# Moisture_Gauge.net
KiCad netlist of a schematic drawn in EAGLE
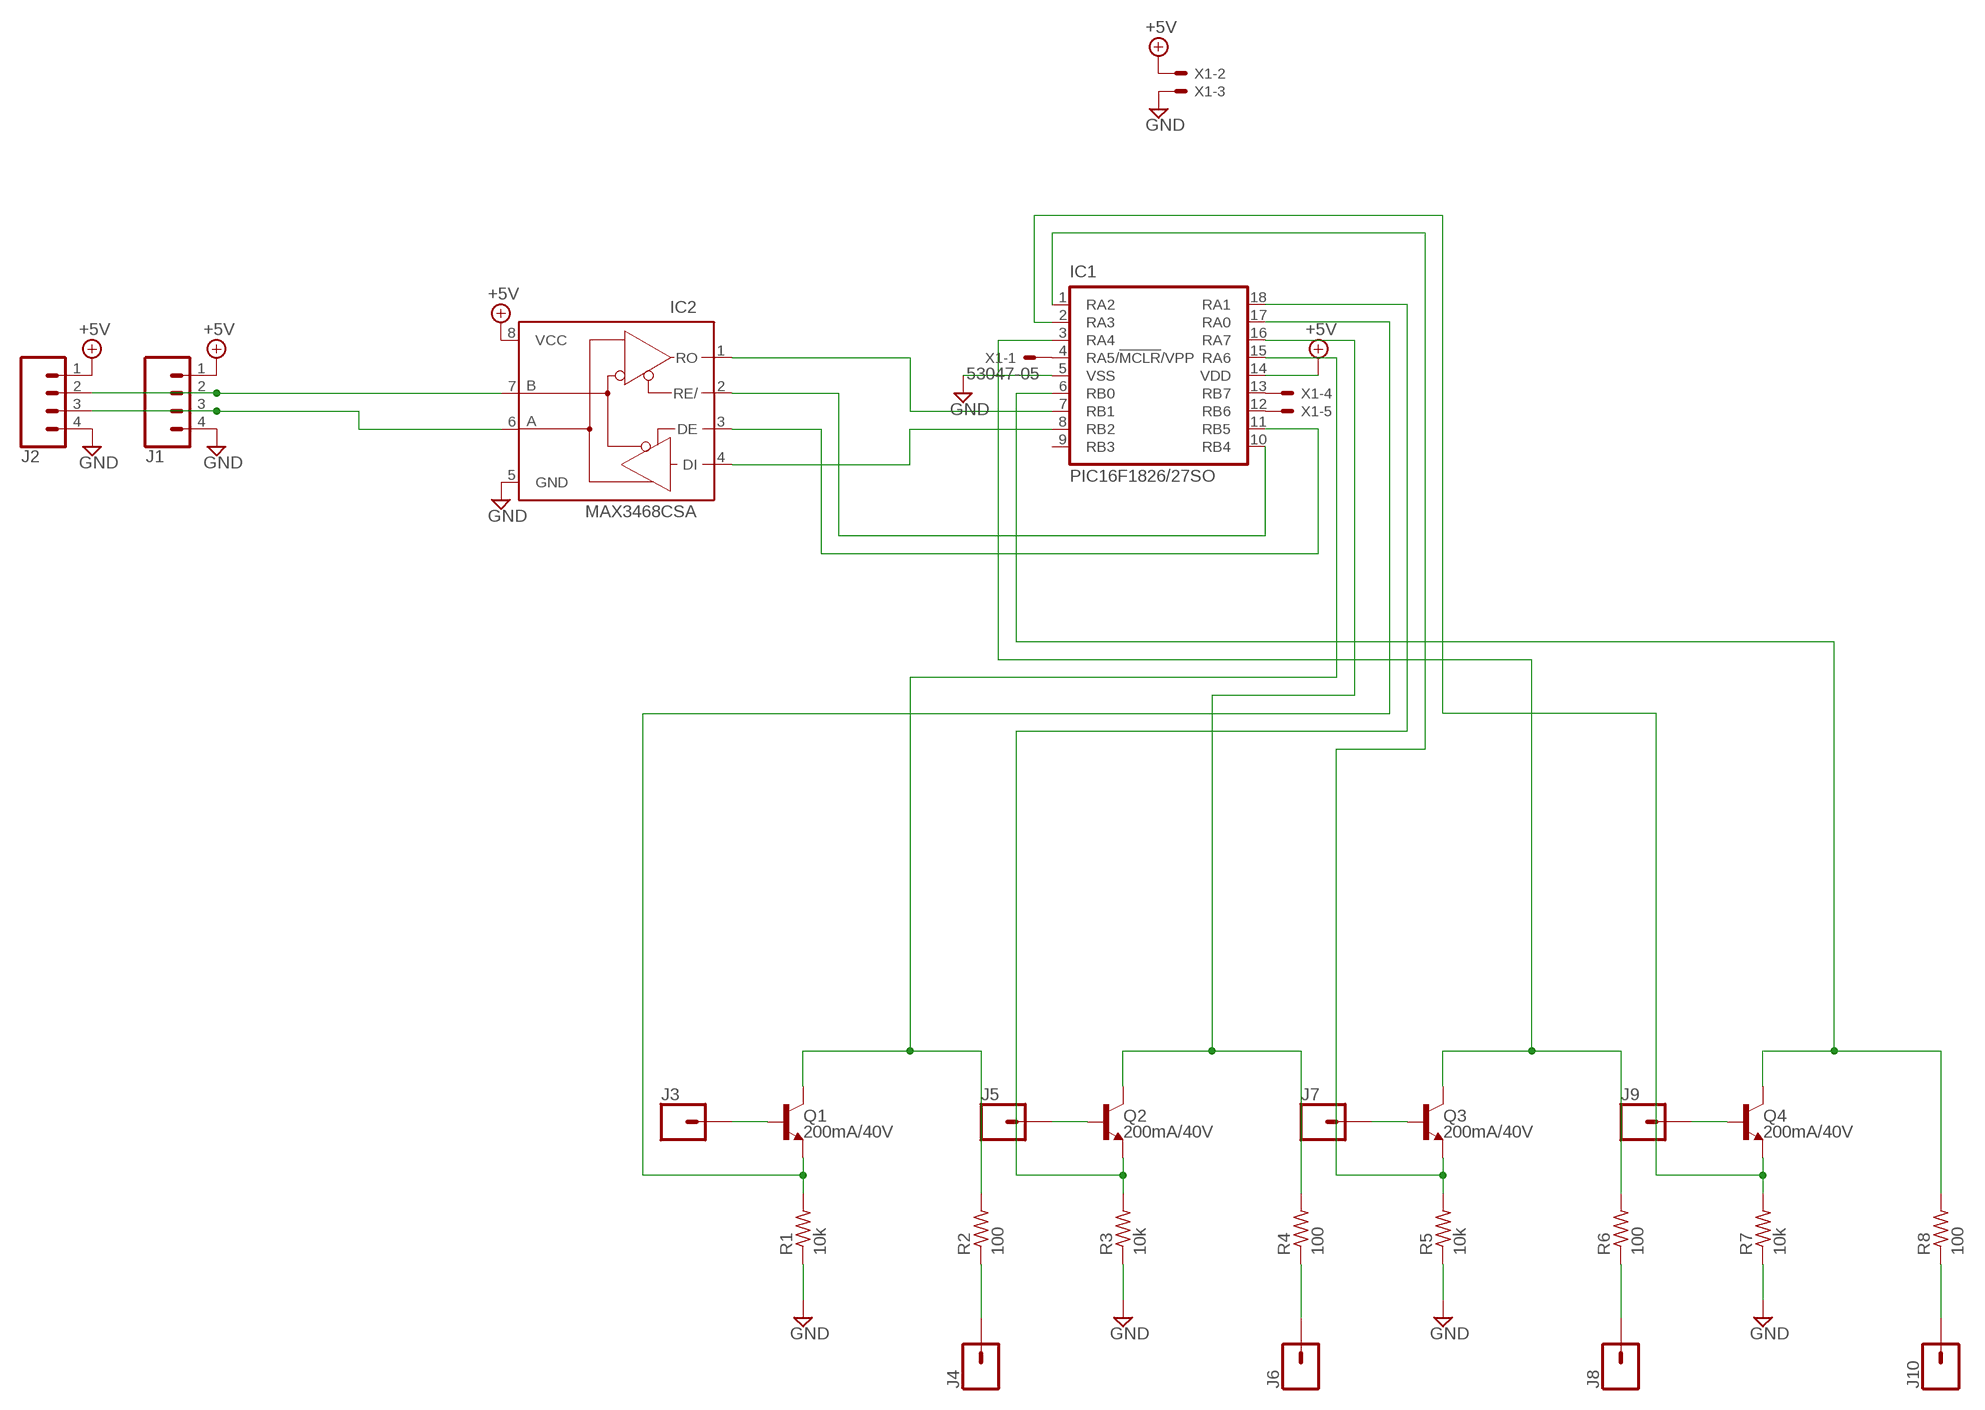
[diagram p0: schematic, sheet 1]

(export (version "E")
  (design (tool "Eeschema 10.0.6"))
  (components
    (comp (ref "IC1")
      (value "PIC16F1826/27SO")
      (footprint "eagle-import:SO-18W")
      (libsource (lib "eagle-import") (part "PIC16F1826/27SO"))
    )
    (comp (ref "IC2")
      (value "MAX3468CSA")
      (footprint "eagle-import:SO08")
      (fields (field (name "MPN") "MAX3468CSA+"))
      (libsource (lib "eagle-import") (part "MAX34SA68C"))
    )
    (comp (ref "J1")
      (value "CONN_04SCREW")
      (footprint "eagle-import:SCREWTERMINAL-3.5MM-4")
      (libsource (lib "eagle-import") (part "CONN_04SCREW"))
    )
    (comp (ref "J2")
      (value "CONN_04SCREW")
      (footprint "eagle-import:SCREWTERMINAL-3.5MM-4")
      (libsource (lib "eagle-import") (part "CONN_04SCREW"))
    )
    (comp (ref "J3")
      (value "CONN_01PTH_2MM")
      (footprint "eagle-import:1X01_2MM")
      (libsource (lib "eagle-import") (part "CONN_01PTH_2MM"))
    )
    (comp (ref "J4")
      (value "CONN_01PTH_2MM")
      (footprint "eagle-import:1X01_2MM")
      (libsource (lib "eagle-import") (part "CONN_01PTH_2MM"))
    )
    (comp (ref "J5")
      (value "CONN_01PTH_2MM")
      (footprint "eagle-import:1X01_2MM")
      (libsource (lib "eagle-import") (part "CONN_01PTH_2MM"))
    )
    (comp (ref "J6")
      (value "CONN_01PTH_2MM")
      (footprint "eagle-import:1X01_2MM")
      (libsource (lib "eagle-import") (part "CONN_01PTH_2MM"))
    )
    (comp (ref "J7")
      (value "CONN_01PTH_2MM")
      (footprint "eagle-import:1X01_2MM")
      (libsource (lib "eagle-import") (part "CONN_01PTH_2MM"))
    )
    (comp (ref "J8")
      (value "CONN_01PTH_2MM")
      (footprint "eagle-import:1X01_2MM")
      (libsource (lib "eagle-import") (part "CONN_01PTH_2MM"))
    )
    (comp (ref "J9")
      (value "CONN_01PTH_2MM")
      (footprint "eagle-import:1X01_2MM")
      (libsource (lib "eagle-import") (part "CONN_01PTH_2MM"))
    )
    (comp (ref "J10")
      (value "CONN_01PTH_2MM")
      (footprint "eagle-import:1X01_2MM")
      (libsource (lib "eagle-import") (part "CONN_01PTH_2MM"))
    )
    (comp (ref "Q1")
      (value "200mA/40V")
      (footprint "eagle-import:TO-92")
      (libsource (lib "eagle-import") (part "TRANS_NPN-2N3904"))
    )
    (comp (ref "Q2")
      (value "200mA/40V")
      (footprint "eagle-import:TO-92")
      (libsource (lib "eagle-import") (part "TRANS_NPN-2N3904"))
    )
    (comp (ref "Q3")
      (value "200mA/40V")
      (footprint "eagle-import:TO-92")
      (libsource (lib "eagle-import") (part "TRANS_NPN-2N3904"))
    )
    (comp (ref "Q4")
      (value "200mA/40V")
      (footprint "eagle-import:TO-92")
      (libsource (lib "eagle-import") (part "TRANS_NPN-2N3904"))
    )
    (comp (ref "R1")
      (value "10k")
      (footprint "eagle-import:M1206")
      (libsource (lib "eagle-import") (part "R-US_M1206"))
    )
    (comp (ref "R2")
      (value "100")
      (footprint "eagle-import:M1206")
      (libsource (lib "eagle-import") (part "R-US_M1206"))
    )
    (comp (ref "R3")
      (value "10k")
      (footprint "eagle-import:M1206")
      (libsource (lib "eagle-import") (part "R-US_M1206"))
    )
    (comp (ref "R4")
      (value "100")
      (footprint "eagle-import:M1206")
      (libsource (lib "eagle-import") (part "R-US_M1206"))
    )
    (comp (ref "R5")
      (value "10k")
      (footprint "eagle-import:M1206")
      (libsource (lib "eagle-import") (part "R-US_M1206"))
    )
    (comp (ref "R6")
      (value "100")
      (footprint "eagle-import:M1206")
      (libsource (lib "eagle-import") (part "R-US_M1206"))
    )
    (comp (ref "R7")
      (value "10k")
      (footprint "eagle-import:M1206")
      (libsource (lib "eagle-import") (part "R-US_M1206"))
    )
    (comp (ref "R8")
      (value "100")
      (footprint "eagle-import:M1206")
      (libsource (lib "eagle-import") (part "R-US_M1206"))
    )
    (comp (ref "X1")
      (value "53047-05")
      (footprint "eagle-import:53047-05")
      (fields (field (name "MF") "MOLEX") (field (name "MPN") "53047-0510"))
      (libsource (lib "eagle-import") (part "53?-05047"))
    )
  )
  (nets
    (net (code "1") (name "+5V") (class "Default")
      (node (ref "IC1") (pin "14") (pinfunction "VDD_14") (pintype "power_in"))
      (node (ref "IC2") (pin "8") (pinfunction "VCC_8") (pintype "power_in"))
      (node (ref "J1") (pin "1") (pinfunction "1_1") (pintype "passive"))
      (node (ref "J2") (pin "1") (pinfunction "1_1") (pintype "passive"))
      (node (ref "X1") (pin "2") (pinfunction "S_2") (pintype "passive"))
    )
    (net (code "2") (name "GND") (class "Default")
      (node (ref "IC1") (pin "5") (pinfunction "VSS_5") (pintype "power_in"))
      (node (ref "IC2") (pin "5") (pinfunction "GND_5") (pintype "power_in"))
      (node (ref "J1") (pin "4") (pinfunction "4_4") (pintype "passive"))
      (node (ref "J2") (pin "4") (pinfunction "4_4") (pintype "passive"))
      (node (ref "R1") (pin "1") (pinfunction "1_1") (pintype "passive"))
      (node (ref "R3") (pin "1") (pinfunction "1_1") (pintype "passive"))
      (node (ref "R5") (pin "1") (pinfunction "1_1") (pintype "passive"))
      (node (ref "R7") (pin "1") (pinfunction "1_1") (pintype "passive"))
      (node (ref "X1") (pin "3") (pinfunction "S_3") (pintype "passive"))
    )
    (net (code "3") (name "Net-(IC1-RA0)") (class "Default")
      (node (ref "IC1") (pin "17") (pinfunction "RA0_17") (pintype "bidirectional"))
      (node (ref "Q1") (pin "1") (pinfunction "E_1") (pintype "passive"))
      (node (ref "R1") (pin "2") (pinfunction "2_2") (pintype "passive"))
    )
    (net (code "4") (name "Net-(IC1-RA1)") (class "Default")
      (node (ref "IC1") (pin "18") (pinfunction "RA1_18") (pintype "bidirectional"))
      (node (ref "Q2") (pin "1") (pinfunction "E_1") (pintype "passive"))
      (node (ref "R3") (pin "2") (pinfunction "2_2") (pintype "passive"))
    )
    (net (code "5") (name "Net-(IC1-RA2)") (class "Default")
      (node (ref "IC1") (pin "1") (pinfunction "RA2_1") (pintype "bidirectional"))
      (node (ref "Q3") (pin "1") (pinfunction "E_1") (pintype "passive"))
      (node (ref "R5") (pin "2") (pinfunction "2_2") (pintype "passive"))
    )
    (net (code "6") (name "Net-(IC1-RA3)") (class "Default")
      (node (ref "IC1") (pin "2") (pinfunction "RA3_2") (pintype "bidirectional"))
      (node (ref "Q4") (pin "1") (pinfunction "E_1") (pintype "passive"))
      (node (ref "R7") (pin "2") (pinfunction "2_2") (pintype "passive"))
    )
    (net (code "7") (name "Net-(IC1-RA4)") (class "Default")
      (node (ref "IC1") (pin "3") (pinfunction "RA4_3") (pintype "bidirectional"))
      (node (ref "Q3") (pin "3") (pinfunction "C_3") (pintype "passive"))
      (node (ref "R6") (pin "2") (pinfunction "2_2") (pintype "passive"))
    )
    (net (code "8") (name "Net-(IC1-RA5{slash}~{MCLR}{slash}VPP)") (class "Default")
      (node (ref "IC1") (pin "4") (pinfunction "RA5/~{MCLR}/VPP_4") (pintype "bidirectional"))
      (node (ref "X1") (pin "1") (pinfunction "S_1") (pintype "passive"))
    )
    (net (code "9") (name "Net-(IC1-RA6)") (class "Default")
      (node (ref "IC1") (pin "15") (pinfunction "RA6_15") (pintype "bidirectional"))
      (node (ref "Q1") (pin "3") (pinfunction "C_3") (pintype "passive"))
      (node (ref "R2") (pin "2") (pinfunction "2_2") (pintype "passive"))
    )
    (net (code "10") (name "Net-(IC1-RA7)") (class "Default")
      (node (ref "IC1") (pin "16") (pinfunction "RA7_16") (pintype "bidirectional"))
      (node (ref "Q2") (pin "3") (pinfunction "C_3") (pintype "passive"))
      (node (ref "R4") (pin "2") (pinfunction "2_2") (pintype "passive"))
    )
    (net (code "11") (name "Net-(IC1-RB0)") (class "Default")
      (node (ref "IC1") (pin "6") (pinfunction "RB0_6") (pintype "bidirectional"))
      (node (ref "Q4") (pin "3") (pinfunction "C_3") (pintype "passive"))
      (node (ref "R8") (pin "2") (pinfunction "2_2") (pintype "passive"))
    )
    (net (code "12") (name "Net-(IC1-RB1)") (class "Default")
      (node (ref "IC1") (pin "7") (pinfunction "RB1_7") (pintype "bidirectional"))
      (node (ref "IC2") (pin "1") (pinfunction "RO_1") (pintype "output"))
    )
    (net (code "13") (name "Net-(IC1-RB2)") (class "Default")
      (node (ref "IC1") (pin "8") (pinfunction "RB2_8") (pintype "bidirectional"))
      (node (ref "IC2") (pin "4") (pinfunction "DI_4") (pintype "input"))
    )
    (net (code "14") (name "Net-(IC1-RB4)") (class "Default")
      (node (ref "IC1") (pin "10") (pinfunction "RB4_10") (pintype "bidirectional"))
      (node (ref "IC2") (pin "2") (pinfunction "RE/_2") (pintype "input"))
    )
    (net (code "15") (name "Net-(IC1-RB5)") (class "Default")
      (node (ref "IC1") (pin "11") (pinfunction "RB5_11") (pintype "bidirectional"))
      (node (ref "IC2") (pin "3") (pinfunction "DE_3") (pintype "input"))
    )
    (net (code "16") (name "Net-(IC1-RB6)") (class "Default")
      (node (ref "IC1") (pin "12") (pinfunction "RB6_12") (pintype "bidirectional"))
      (node (ref "X1") (pin "5") (pinfunction "S_5") (pintype "passive"))
    )
    (net (code "17") (name "Net-(IC1-RB7)") (class "Default")
      (node (ref "IC1") (pin "13") (pinfunction "RB7_13") (pintype "bidirectional"))
      (node (ref "X1") (pin "4") (pinfunction "S_4") (pintype "passive"))
    )
    (net (code "18") (name "Net-(IC2-A)") (class "Default")
      (node (ref "IC2") (pin "6") (pinfunction "A_6") (pintype "passive"))
      (node (ref "J1") (pin "3") (pinfunction "3_3") (pintype "passive"))
      (node (ref "J2") (pin "3") (pinfunction "3_3") (pintype "passive"))
    )
    (net (code "19") (name "Net-(IC2-B)") (class "Default")
      (node (ref "IC2") (pin "7") (pinfunction "B_7") (pintype "passive"))
      (node (ref "J1") (pin "2") (pinfunction "2_2") (pintype "passive"))
      (node (ref "J2") (pin "2") (pinfunction "2_2") (pintype "passive"))
    )
    (net (code "20") (name "Net-(J4-Pad1)") (class "Default")
      (node (ref "J4") (pin "1") (pinfunction "1_1") (pintype "passive"))
      (node (ref "R2") (pin "1") (pinfunction "1_1") (pintype "passive"))
    )
    (net (code "21") (name "Net-(J6-Pad1)") (class "Default")
      (node (ref "J6") (pin "1") (pinfunction "1_1") (pintype "passive"))
      (node (ref "R4") (pin "1") (pinfunction "1_1") (pintype "passive"))
    )
    (net (code "22") (name "Net-(J8-Pad1)") (class "Default")
      (node (ref "J8") (pin "1") (pinfunction "1_1") (pintype "passive"))
      (node (ref "R6") (pin "1") (pinfunction "1_1") (pintype "passive"))
    )
    (net (code "23") (name "Net-(J10-Pad1)") (class "Default")
      (node (ref "J10") (pin "1") (pinfunction "1_1") (pintype "passive"))
      (node (ref "R8") (pin "1") (pinfunction "1_1") (pintype "passive"))
    )
    (net (code "24") (name "Net-(Q1-B)") (class "Default")
      (node (ref "J3") (pin "1") (pinfunction "1_1") (pintype "passive"))
      (node (ref "Q1") (pin "2") (pinfunction "B_2") (pintype "passive"))
    )
    (net (code "25") (name "Net-(Q2-B)") (class "Default")
      (node (ref "J5") (pin "1") (pinfunction "1_1") (pintype "passive"))
      (node (ref "Q2") (pin "2") (pinfunction "B_2") (pintype "passive"))
    )
    (net (code "26") (name "Net-(Q3-B)") (class "Default")
      (node (ref "J7") (pin "1") (pinfunction "1_1") (pintype "passive"))
      (node (ref "Q3") (pin "2") (pinfunction "B_2") (pintype "passive"))
    )
    (net (code "27") (name "Net-(Q4-B)") (class "Default")
      (node (ref "J9") (pin "1") (pinfunction "1_1") (pintype "passive"))
      (node (ref "Q4") (pin "2") (pinfunction "B_2") (pintype "passive"))
    )
    (net (code "28") (name "unconnected-(IC1-RB3-Pad9)") (class "Default")
      (node (ref "IC1") (pin "9") (pinfunction "RB3_9") (pintype "bidirectional"))
    )
  )
)
